# driver.net
KiCad netlist of a schematic drawn in EAGLE
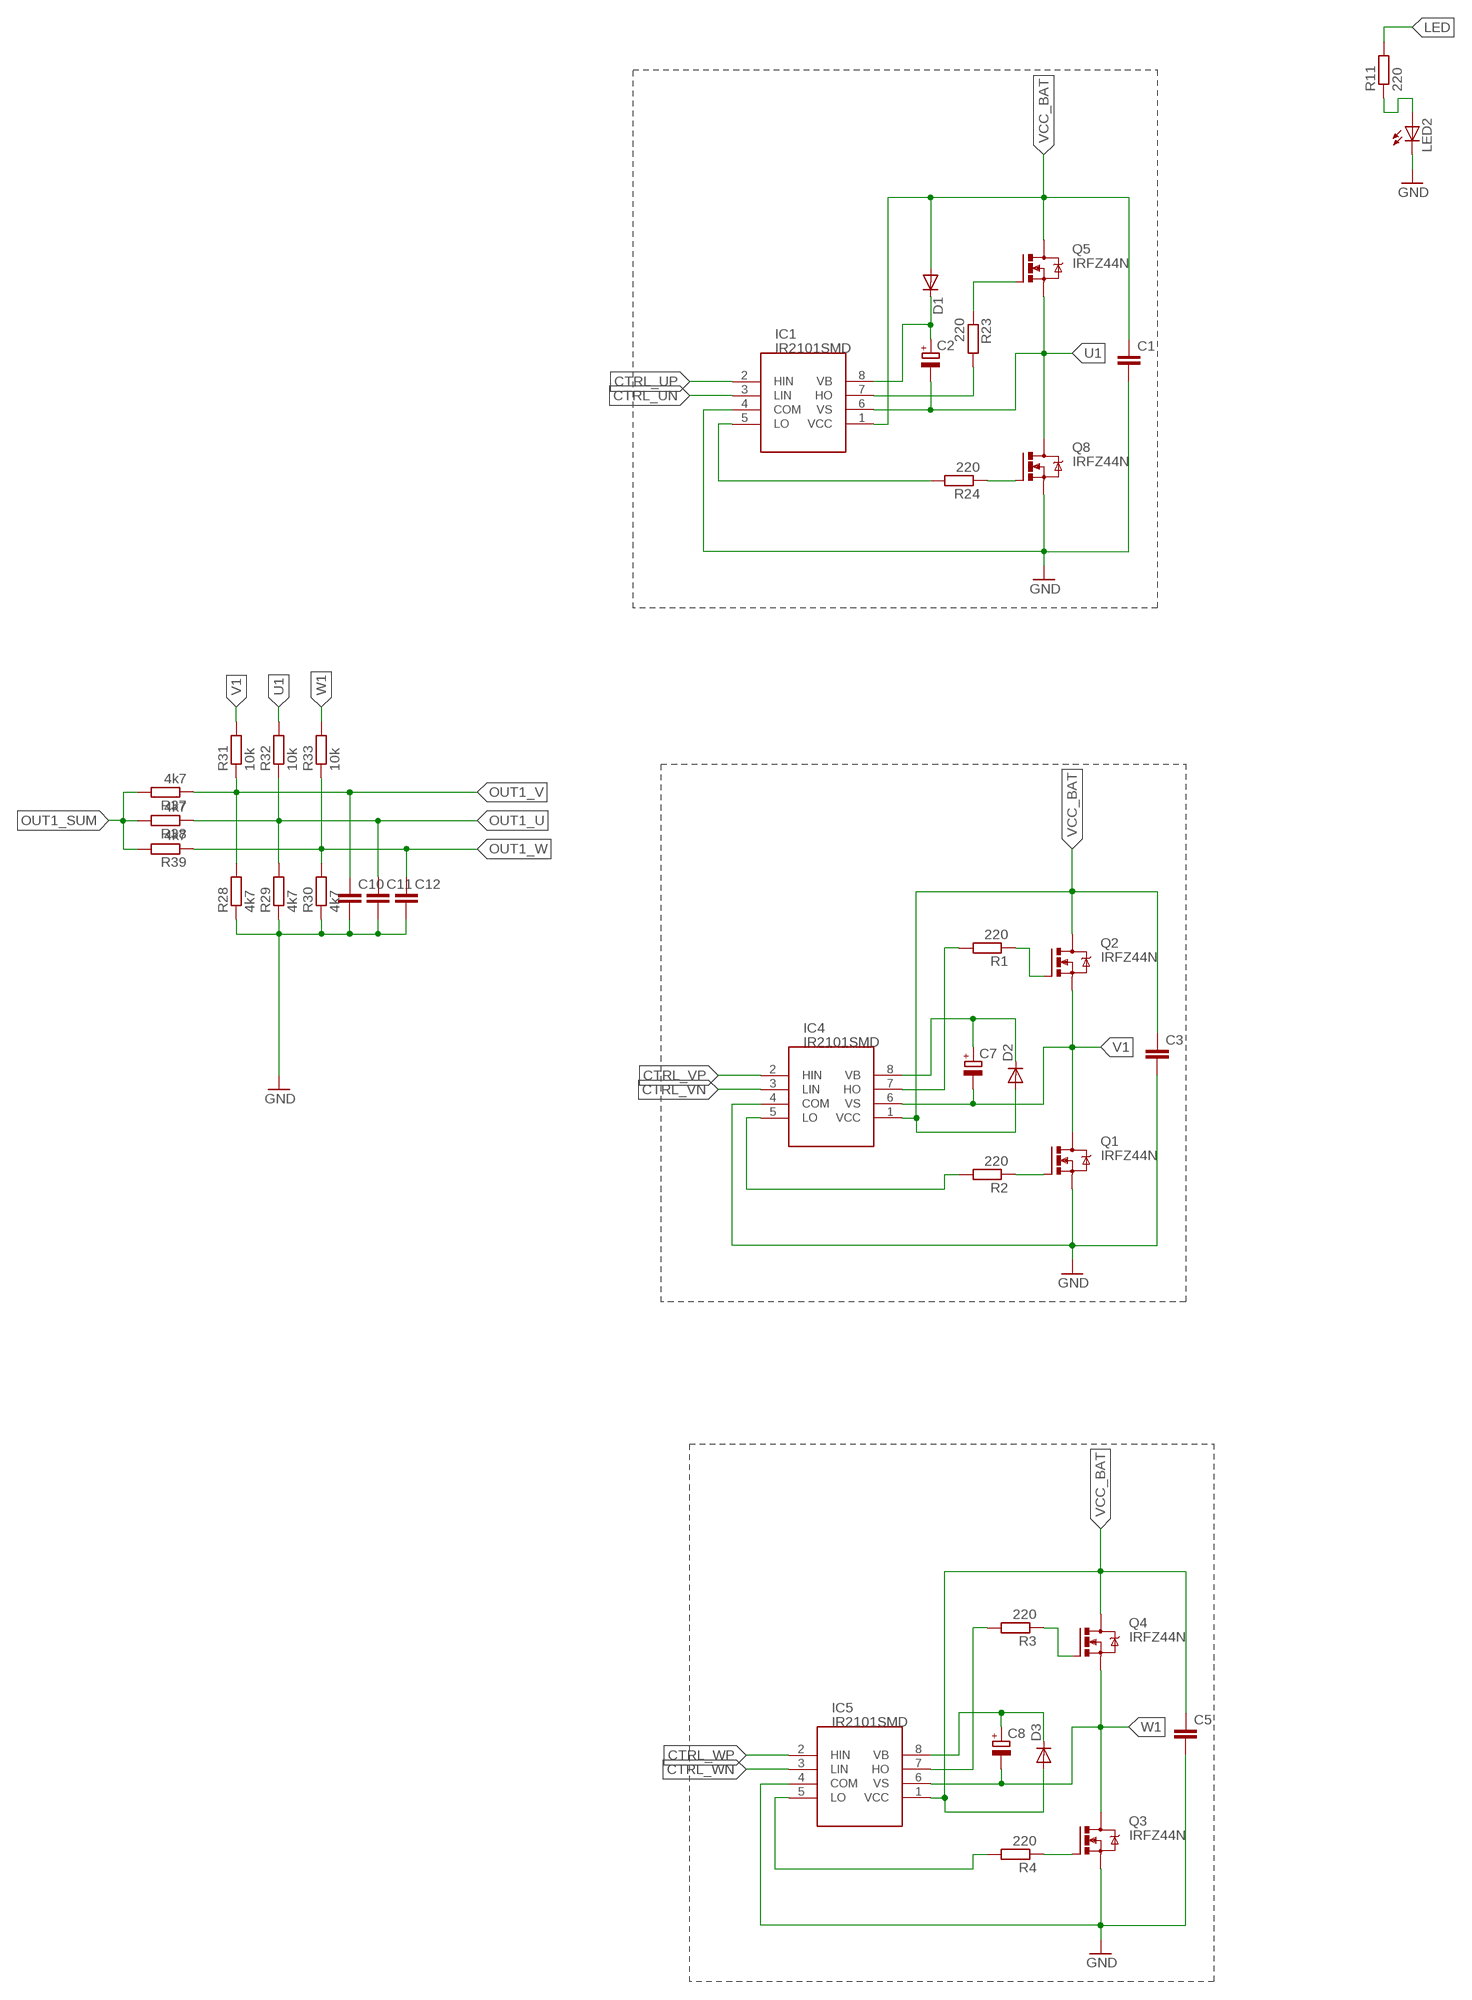
[diagram p0: schematic, sheet 1, part 1 of 2]
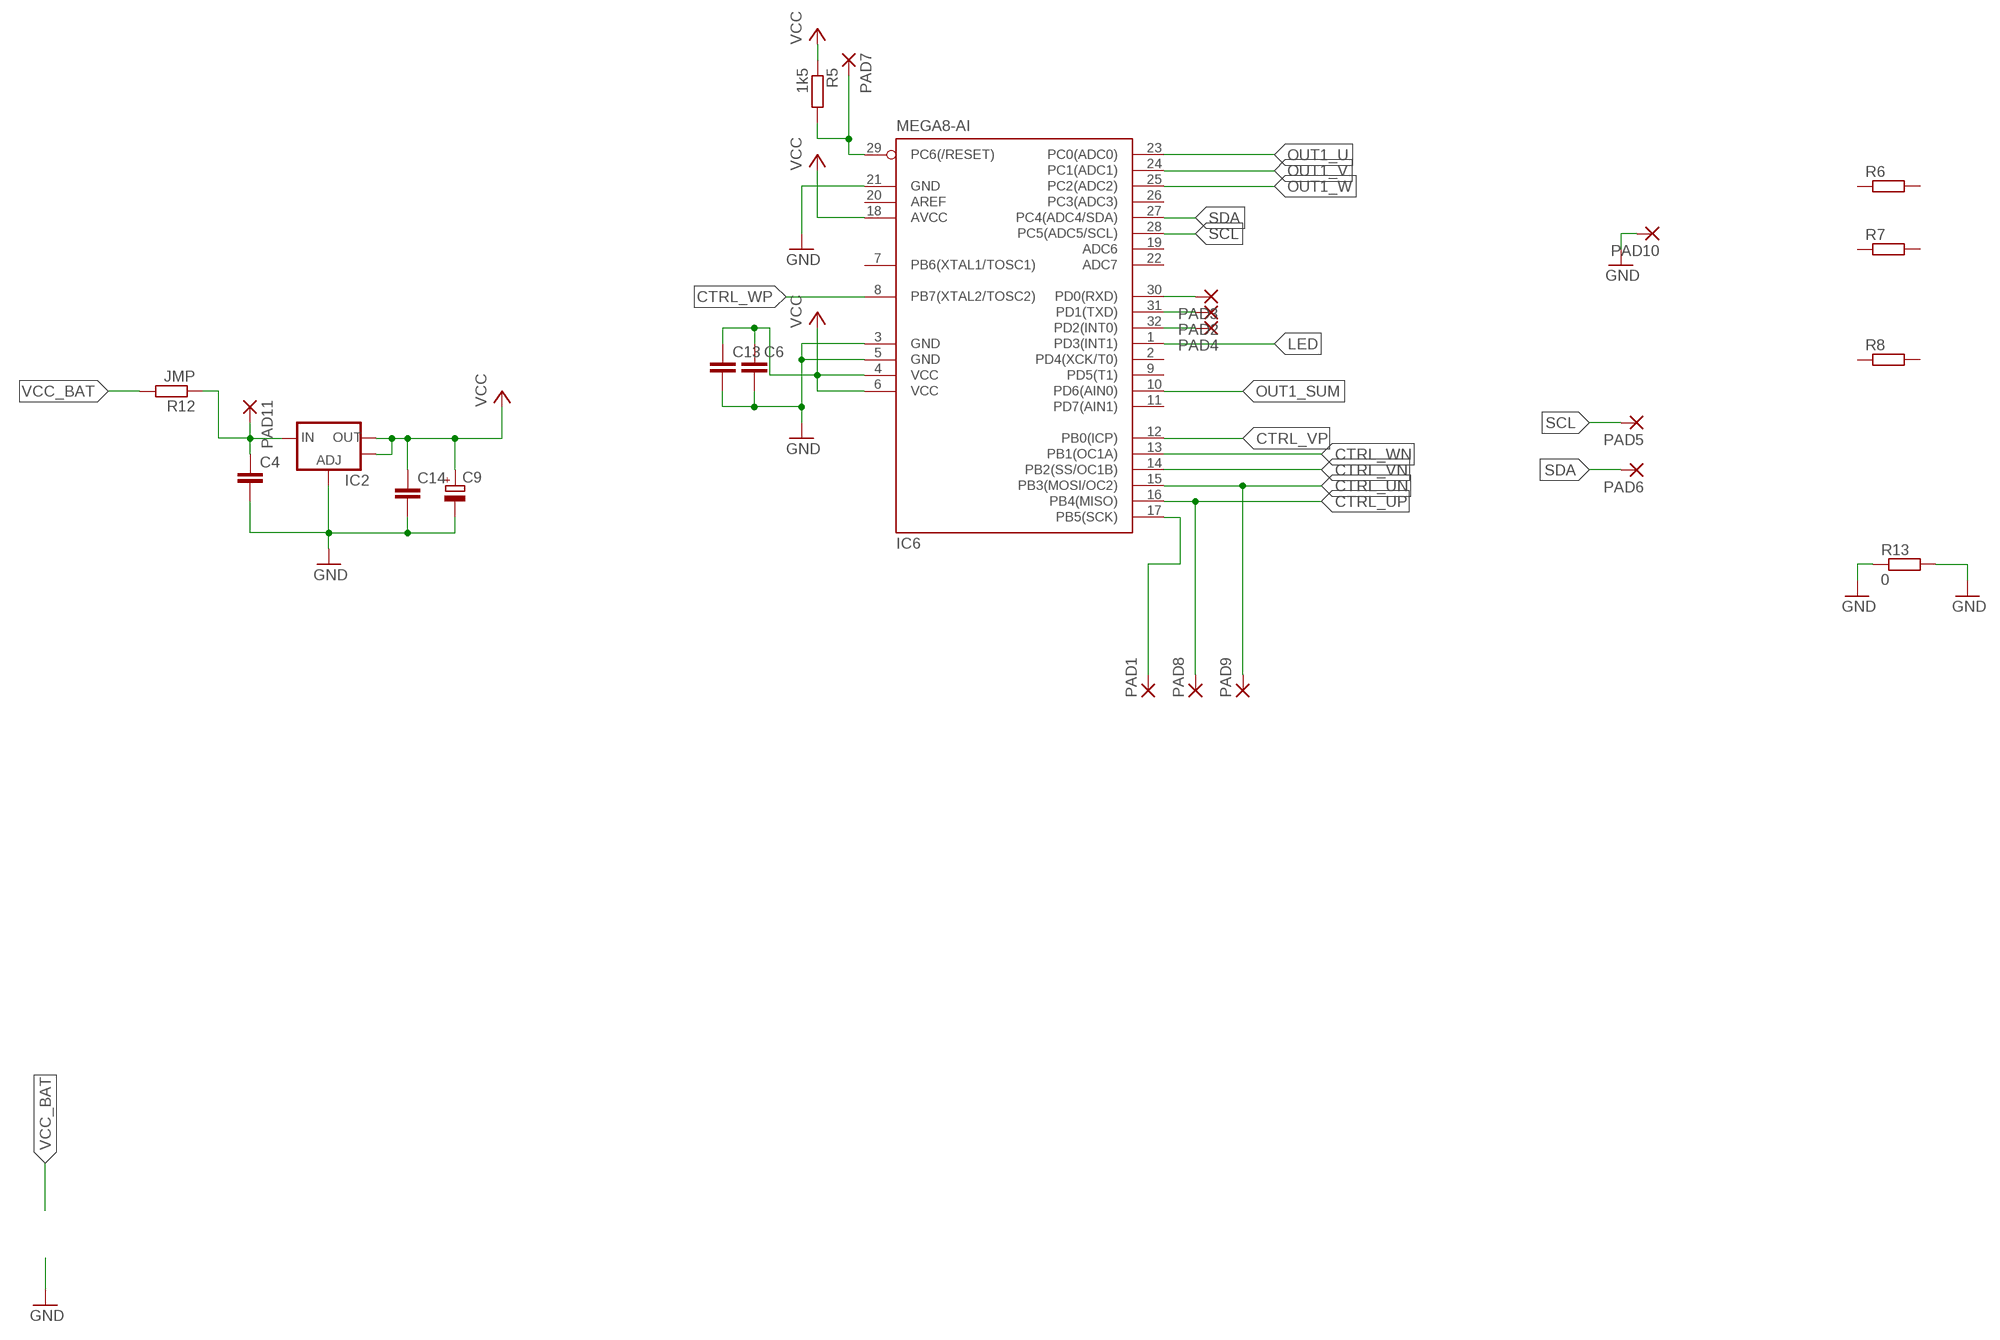
[diagram p1: schematic, sheet 1, part 2 of 2]

(export (version "E")
  (design (tool "Eeschema 10.0.6"))
  (components
    (comp (ref "C1")
      (value "C-EUC0805")
      (footprint "eagle-import:C0805")
      (libsource (lib "eagle-import") (part "C-EUC0805"))
    )
    (comp (ref "C2")
      (value "CPOL-EUSANYO_SMD_A5")
      (footprint "eagle-import:SANYO-OSCON_SMD_A5")
      (libsource (lib "eagle-import") (part "CPOL-EUSANYO_SMD_A5"))
    )
    (comp (ref "C3")
      (value "C-EUC0805")
      (footprint "eagle-import:C0805")
      (libsource (lib "eagle-import") (part "C-EUC0805"))
    )
    (comp (ref "C4")
      (value "C-EUC0805")
      (footprint "eagle-import:C0805")
      (libsource (lib "eagle-import") (part "C-EUC0805"))
    )
    (comp (ref "C5")
      (value "C-EUC0805")
      (footprint "eagle-import:C0805")
      (libsource (lib "eagle-import") (part "C-EUC0805"))
    )
    (comp (ref "C6")
      (value "C-EUC0805")
      (footprint "eagle-import:C0805")
      (libsource (lib "eagle-import") (part "C-EUC0805"))
    )
    (comp (ref "C7")
      (value "CPOL-EUSANYO_SMD_A5")
      (footprint "eagle-import:SANYO-OSCON_SMD_A5")
      (libsource (lib "eagle-import") (part "CPOL-EUSANYO_SMD_A5"))
    )
    (comp (ref "C8")
      (value "CPOL-EUSANYO_SMD_A5")
      (footprint "eagle-import:SANYO-OSCON_SMD_A5")
      (libsource (lib "eagle-import") (part "CPOL-EUSANYO_SMD_A5"))
    )
    (comp (ref "C9")
      (value "CPOL-EUSANYO_SMD_A5")
      (footprint "eagle-import:SANYO-OSCON_SMD_A5")
      (libsource (lib "eagle-import") (part "CPOL-EUSANYO_SMD_A5"))
    )
    (comp (ref "C10")
      (value "C-EUC0805")
      (footprint "eagle-import:C0805")
      (libsource (lib "eagle-import") (part "C-EUC0805"))
    )
    (comp (ref "C11")
      (value "C-EUC1206")
      (footprint "eagle-import:C1206")
      (libsource (lib "eagle-import") (part "C-EUC1206"))
    )
    (comp (ref "C12")
      (value "C-EUC1206")
      (footprint "eagle-import:C1206")
      (libsource (lib "eagle-import") (part "C-EUC1206"))
    )
    (comp (ref "C13")
      (value "C-EUC0805")
      (footprint "eagle-import:C0805")
      (libsource (lib "eagle-import") (part "C-EUC0805"))
    )
    (comp (ref "C14")
      (value "C-EUC0805")
      (footprint "eagle-import:C0805")
      (libsource (lib "eagle-import") (part "C-EUC0805"))
    )
    (comp (ref "D1")
      (value "DIODE-MINIMELF")
      (footprint "eagle-import:MINIMELF")
      (libsource (lib "eagle-import") (part "DIODE-MINIMELF"))
    )
    (comp (ref "D2")
      (value "DIODE-MINIMELF")
      (footprint "eagle-import:MINIMELF")
      (libsource (lib "eagle-import") (part "DIODE-MINIMELF"))
    )
    (comp (ref "D3")
      (value "DIODE-MINIMELF")
      (footprint "eagle-import:MINIMELF")
      (libsource (lib "eagle-import") (part "DIODE-MINIMELF"))
    )
    (comp (ref "IC1")
      (value "IR2101SMD")
      (footprint "eagle-import:SO08")
      (libsource (lib "eagle-import") (part "IR2101SMD"))
    )
    (comp (ref "IC2")
      (value "V_REG_LM1117SOT223")
      (footprint "eagle-import:SOT223")
      (libsource (lib "eagle-import") (part "V_REG_LM1117SOT223"))
    )
    (comp (ref "IC4")
      (value "IR2101SMD")
      (footprint "eagle-import:SO08")
      (libsource (lib "eagle-import") (part "IR2101SMD"))
    )
    (comp (ref "IC5")
      (value "IR2101SMD")
      (footprint "eagle-import:SO08")
      (libsource (lib "eagle-import") (part "IR2101SMD"))
    )
    (comp (ref "IC6")
      (value "MEGA8-AI")
      (footprint "eagle-import:TQFP32-08")
      (fields (field (name "MPN") "ATMEGA8-16AU"))
      (libsource (lib "eagle-import") (part "MEGA8-AI"))
    )
    (comp (ref "LED2")
      (value "LEDCHIPLED_0805")
      (footprint "eagle-import:CHIPLED_0805")
      (libsource (lib "eagle-import") (part "LEDCHIPLED_0805"))
    )
    (comp (ref "PAD1")
      (value "SMD2")
      (footprint "eagle-import:SMD1,27-2,54")
      (libsource (lib "eagle-import") (part "SMD2"))
    )
    (comp (ref "PAD2")
      (value "SMD2")
      (footprint "eagle-import:SMD1,27-2,54")
      (libsource (lib "eagle-import") (part "SMD2"))
    )
    (comp (ref "PAD3")
      (value "SMD2")
      (footprint "eagle-import:SMD1,27-2,54")
      (libsource (lib "eagle-import") (part "SMD2"))
    )
    (comp (ref "PAD4")
      (value "SMD2")
      (footprint "eagle-import:SMD1,27-2,54")
      (libsource (lib "eagle-import") (part "SMD2"))
    )
    (comp (ref "PAD5")
      (value "SMD5")
      (footprint "eagle-import:SMD2,54-5,08")
      (libsource (lib "eagle-import") (part "SMD5"))
    )
    (comp (ref "PAD6")
      (value "SMD5")
      (footprint "eagle-import:SMD2,54-5,08")
      (libsource (lib "eagle-import") (part "SMD5"))
    )
    (comp (ref "PAD7")
      (value "SMD2")
      (footprint "eagle-import:SMD1,27-2,54")
      (libsource (lib "eagle-import") (part "SMD2"))
    )
    (comp (ref "PAD8")
      (value "SMD2")
      (footprint "eagle-import:SMD1,27-2,54")
      (libsource (lib "eagle-import") (part "SMD2"))
    )
    (comp (ref "PAD9")
      (value "SMD2")
      (footprint "eagle-import:SMD1,27-2,54")
      (libsource (lib "eagle-import") (part "SMD2"))
    )
    (comp (ref "PAD10")
      (value "SMD5")
      (footprint "eagle-import:SMD2,54-5,08")
      (libsource (lib "eagle-import") (part "SMD5"))
    )
    (comp (ref "PAD11")
      (value "SMD5")
      (footprint "eagle-import:SMD2,54-5,08")
      (libsource (lib "eagle-import") (part "SMD5"))
    )
    (comp (ref "Q1")
      (value "IRFZ44N")
      (footprint "eagle-import:TO220BH-FILL")
      (libsource (lib "eagle-import") (part "IRFZ48"))
    )
    (comp (ref "Q2")
      (value "IRFZ44N")
      (footprint "eagle-import:TO220BH-FILL")
      (libsource (lib "eagle-import") (part "IRFZ48"))
    )
    (comp (ref "Q3")
      (value "IRFZ44N")
      (footprint "eagle-import:TO220BH-FILL")
      (libsource (lib "eagle-import") (part "IRFZ48"))
    )
    (comp (ref "Q4")
      (value "IRFZ44N")
      (footprint "eagle-import:TO220BH-FILL")
      (libsource (lib "eagle-import") (part "IRFZ48"))
    )
    (comp (ref "Q5")
      (value "IRFZ44N")
      (footprint "eagle-import:TO220BH-FILL")
      (libsource (lib "eagle-import") (part "IRFZ48"))
    )
    (comp (ref "Q8")
      (value "IRFZ44N")
      (footprint "eagle-import:TO220BH-FILL")
      (libsource (lib "eagle-import") (part "IRFZ48"))
    )
    (comp (ref "R1")
      (value "220")
      (footprint "eagle-import:R1206")
      (libsource (lib "eagle-import") (part "R-EU_R1206"))
    )
    (comp (ref "R2")
      (value "220")
      (footprint "eagle-import:R1206")
      (libsource (lib "eagle-import") (part "R-EU_R1206"))
    )
    (comp (ref "R3")
      (value "220")
      (footprint "eagle-import:R1206")
      (libsource (lib "eagle-import") (part "R-EU_R1206"))
    )
    (comp (ref "R4")
      (value "220")
      (footprint "eagle-import:R1206")
      (libsource (lib "eagle-import") (part "R-EU_R1206"))
    )
    (comp (ref "R5")
      (value "1k5")
      (footprint "eagle-import:R1206")
      (libsource (lib "eagle-import") (part "R-EU_R1206"))
    )
    (comp (ref "R6")
      (value "R-EU_R1206")
      (footprint "eagle-import:R1206")
      (libsource (lib "eagle-import") (part "R-EU_R1206"))
    )
    (comp (ref "R7")
      (value "R-EU_R1206")
      (footprint "eagle-import:R1206")
      (libsource (lib "eagle-import") (part "R-EU_R1206"))
    )
    (comp (ref "R8")
      (value "R-EU_R1206")
      (footprint "eagle-import:R1206")
      (libsource (lib "eagle-import") (part "R-EU_R1206"))
    )
    (comp (ref "R11")
      (value "220")
      (footprint "eagle-import:R0805")
      (libsource (lib "eagle-import") (part "resistor_R-EU_R0805"))
    )
    (comp (ref "R12")
      (value "JMP")
      (footprint "eagle-import:R0805")
      (libsource (lib "eagle-import") (part "resistor_R-EU_R0805"))
    )
    (comp (ref "R13")
      (value "0")
      (footprint "eagle-import:R1206")
      (libsource (lib "eagle-import") (part "R-EU_R1206"))
    )
    (comp (ref "R23")
      (value "220")
      (footprint "eagle-import:R1206")
      (libsource (lib "eagle-import") (part "R-EU_R1206"))
    )
    (comp (ref "R24")
      (value "220")
      (footprint "eagle-import:R1206")
      (libsource (lib "eagle-import") (part "R-EU_R1206"))
    )
    (comp (ref "R28")
      (value "4k7")
      (footprint "eagle-import:R0805")
      (libsource (lib "eagle-import") (part "R-EU_R0805"))
    )
    (comp (ref "R29")
      (value "4k7")
      (footprint "eagle-import:R1206")
      (libsource (lib "eagle-import") (part "R-EU_R1206"))
    )
    (comp (ref "R30")
      (value "4k7")
      (footprint "eagle-import:R1206")
      (libsource (lib "eagle-import") (part "R-EU_R1206"))
    )
    (comp (ref "R31")
      (value "10k")
      (footprint "eagle-import:R0805")
      (libsource (lib "eagle-import") (part "R-EU_R0805"))
    )
    (comp (ref "R32")
      (value "10k")
      (footprint "eagle-import:R1206")
      (libsource (lib "eagle-import") (part "R-EU_R1206"))
    )
    (comp (ref "R33")
      (value "10k")
      (footprint "eagle-import:R1206")
      (libsource (lib "eagle-import") (part "R-EU_R1206"))
    )
    (comp (ref "R37")
      (value "4k7")
      (footprint "eagle-import:R0805")
      (libsource (lib "eagle-import") (part "R-EU_R0805"))
    )
    (comp (ref "R38")
      (value "4k7")
      (footprint "eagle-import:R0805")
      (libsource (lib "eagle-import") (part "R-EU_R0805"))
    )
    (comp (ref "R39")
      (value "4k7")
      (footprint "eagle-import:R1206")
      (libsource (lib "eagle-import") (part "R-EU_R1206"))
    )
  )
  (nets
    (net (code "1") (name "CTRL_UN") (class "Default")
      (node (ref "IC1") (pin "3") (pinfunction "LIN_3") (pintype "bidirectional"))
      (node (ref "IC6") (pin "15") (pinfunction "PB3(MOSI/OC2)_15") (pintype "bidirectional"))
      (node (ref "PAD9") (pin "1") (pinfunction "P_1") (pintype "passive"))
    )
    (net (code "2") (name "CTRL_UP") (class "Default")
      (node (ref "IC1") (pin "2") (pinfunction "HIN_2") (pintype "bidirectional"))
      (node (ref "IC6") (pin "16") (pinfunction "PB4(MISO)_16") (pintype "bidirectional"))
      (node (ref "PAD8") (pin "1") (pinfunction "P_1") (pintype "passive"))
    )
    (net (code "3") (name "CTRL_VN") (class "Default")
      (node (ref "IC4") (pin "3") (pinfunction "LIN_3") (pintype "bidirectional"))
      (node (ref "IC6") (pin "14") (pinfunction "PB2(SS/OC1B)_14") (pintype "bidirectional"))
    )
    (net (code "4") (name "CTRL_VP") (class "Default")
      (node (ref "IC4") (pin "2") (pinfunction "HIN_2") (pintype "bidirectional"))
      (node (ref "IC6") (pin "12") (pinfunction "PB0(ICP)_12") (pintype "bidirectional"))
    )
    (net (code "5") (name "CTRL_WN") (class "Default")
      (node (ref "IC5") (pin "3") (pinfunction "LIN_3") (pintype "bidirectional"))
      (node (ref "IC6") (pin "13") (pinfunction "PB1(OC1A)_13") (pintype "bidirectional"))
    )
    (net (code "6") (name "CTRL_WP") (class "Default")
      (node (ref "IC5") (pin "2") (pinfunction "HIN_2") (pintype "bidirectional"))
      (node (ref "IC6") (pin "8") (pinfunction "PB7(XTAL2/TOSC2)_8") (pintype "bidirectional"))
    )
    (net (code "7") (name "GND") (class "Default")
      (node (ref "C1") (pin "2") (pinfunction "2_2") (pintype "passive"))
      (node (ref "C10") (pin "2") (pinfunction "2_2") (pintype "passive"))
      (node (ref "C11") (pin "2") (pinfunction "2_2") (pintype "passive"))
      (node (ref "C12") (pin "2") (pinfunction "2_2") (pintype "passive"))
      (node (ref "C13") (pin "2") (pinfunction "2_2") (pintype "passive"))
      (node (ref "C14") (pin "2") (pinfunction "2_2") (pintype "passive"))
      (node (ref "C3") (pin "2") (pinfunction "2_2") (pintype "passive"))
      (node (ref "C4") (pin "2") (pinfunction "2_2") (pintype "passive"))
      (node (ref "C5") (pin "2") (pinfunction "2_2") (pintype "passive"))
      (node (ref "C6") (pin "2") (pinfunction "2_2") (pintype "passive"))
      (node (ref "C9") (pin "-") (pinfunction "-_-") (pintype "passive"))
      (node (ref "IC1") (pin "4") (pinfunction "COM_4") (pintype "bidirectional"))
      (node (ref "IC2") (pin "1") (pinfunction "ADJ_1") (pintype "input"))
      (node (ref "IC4") (pin "4") (pinfunction "COM_4") (pintype "bidirectional"))
      (node (ref "IC5") (pin "4") (pinfunction "COM_4") (pintype "bidirectional"))
      (node (ref "IC6") (pin "21") (pinfunction "GND_21") (pintype "power_in"))
      (node (ref "IC6") (pin "3") (pinfunction "GND_3") (pintype "power_in"))
      (node (ref "IC6") (pin "5") (pinfunction "GND_5") (pintype "power_in"))
      (node (ref "LED2") (pin "C") (pinfunction "C_C") (pintype "passive"))
      (node (ref "PAD10") (pin "1") (pinfunction "P_1") (pintype "passive"))
      (node (ref "Q1") (pin "S") (pinfunction "S_S") (pintype "passive"))
      (node (ref "Q3") (pin "S") (pinfunction "S_S") (pintype "passive"))
      (node (ref "Q8") (pin "S") (pinfunction "S_S") (pintype "passive"))
      (node (ref "R13") (pin "1") (pinfunction "1_1") (pintype "passive"))
      (node (ref "R13") (pin "2") (pinfunction "2_2") (pintype "passive"))
      (node (ref "R28") (pin "1") (pinfunction "1_1") (pintype "passive"))
      (node (ref "R29") (pin "1") (pinfunction "1_1") (pintype "passive"))
      (node (ref "R30") (pin "1") (pinfunction "1_1") (pintype "passive"))
    )
    (net (code "8") (name "LED") (class "Default")
      (node (ref "IC6") (pin "1") (pinfunction "PD3(INT1)_1") (pintype "bidirectional"))
      (node (ref "R11") (pin "2") (pinfunction "2_2") (pintype "passive"))
    )
    (net (code "9") (name "Net-(IC1-HO)") (class "Default")
      (node (ref "IC1") (pin "7") (pinfunction "HO_7") (pintype "bidirectional"))
      (node (ref "R23") (pin "2") (pinfunction "2_2") (pintype "passive"))
    )
    (net (code "10") (name "Net-(IC1-LO)") (class "Default")
      (node (ref "IC1") (pin "5") (pinfunction "LO_5") (pintype "bidirectional"))
      (node (ref "R24") (pin "2") (pinfunction "2_2") (pintype "passive"))
    )
    (net (code "11") (name "Net-(IC1-VB)") (class "Default")
      (node (ref "C2") (pin "+") (pinfunction "+_+") (pintype "passive"))
      (node (ref "D1") (pin "C") (pinfunction "C_C") (pintype "passive"))
      (node (ref "IC1") (pin "8") (pinfunction "VB_8") (pintype "bidirectional"))
    )
    (net (code "12") (name "Net-(IC2-IN)") (class "Default")
      (node (ref "C4") (pin "1") (pinfunction "1_1") (pintype "passive"))
      (node (ref "IC2") (pin "3") (pinfunction "IN_3") (pintype "input"))
      (node (ref "PAD11") (pin "1") (pinfunction "P_1") (pintype "passive"))
      (node (ref "R12") (pin "1") (pinfunction "1_1") (pintype "passive"))
    )
    (net (code "13") (name "Net-(IC4-HO)") (class "Default")
      (node (ref "IC4") (pin "7") (pinfunction "HO_7") (pintype "bidirectional"))
      (node (ref "R1") (pin "2") (pinfunction "2_2") (pintype "passive"))
    )
    (net (code "14") (name "Net-(IC4-LO)") (class "Default")
      (node (ref "IC4") (pin "5") (pinfunction "LO_5") (pintype "bidirectional"))
      (node (ref "R2") (pin "2") (pinfunction "2_2") (pintype "passive"))
    )
    (net (code "15") (name "Net-(IC4-VB)") (class "Default")
      (node (ref "C7") (pin "+") (pinfunction "+_+") (pintype "passive"))
      (node (ref "D2") (pin "C") (pinfunction "C_C") (pintype "passive"))
      (node (ref "IC4") (pin "8") (pinfunction "VB_8") (pintype "bidirectional"))
    )
    (net (code "16") (name "Net-(IC5-HO)") (class "Default")
      (node (ref "IC5") (pin "7") (pinfunction "HO_7") (pintype "bidirectional"))
      (node (ref "R3") (pin "2") (pinfunction "2_2") (pintype "passive"))
    )
    (net (code "17") (name "Net-(IC5-LO)") (class "Default")
      (node (ref "IC5") (pin "5") (pinfunction "LO_5") (pintype "bidirectional"))
      (node (ref "R4") (pin "2") (pinfunction "2_2") (pintype "passive"))
    )
    (net (code "18") (name "Net-(IC5-VB)") (class "Default")
      (node (ref "C8") (pin "+") (pinfunction "+_+") (pintype "passive"))
      (node (ref "D3") (pin "C") (pinfunction "C_C") (pintype "passive"))
      (node (ref "IC5") (pin "8") (pinfunction "VB_8") (pintype "bidirectional"))
    )
    (net (code "19") (name "Net-(IC6-PB5(SCK))") (class "Default")
      (node (ref "IC6") (pin "17") (pinfunction "PB5(SCK)_17") (pintype "bidirectional"))
      (node (ref "PAD1") (pin "1") (pinfunction "P_1") (pintype "passive"))
    )
    (net (code "20") (name "Net-(IC6-PC6({slash}RESET))") (class "Default")
      (node (ref "IC6") (pin "29") (pinfunction "PC6(/RESET)_29") (pintype "bidirectional"))
      (node (ref "PAD7") (pin "1") (pinfunction "P_1") (pintype "passive"))
      (node (ref "R5") (pin "2") (pinfunction "2_2") (pintype "passive"))
    )
    (net (code "21") (name "Net-(IC6-PD0(RXD))") (class "Default")
      (node (ref "IC6") (pin "30") (pinfunction "PD0(RXD)_30") (pintype "bidirectional"))
      (node (ref "PAD3") (pin "1") (pinfunction "P_1") (pintype "passive"))
    )
    (net (code "22") (name "Net-(IC6-PD1(TXD))") (class "Default")
      (node (ref "IC6") (pin "31") (pinfunction "PD1(TXD)_31") (pintype "bidirectional"))
      (node (ref "PAD2") (pin "1") (pinfunction "P_1") (pintype "passive"))
    )
    (net (code "23") (name "Net-(IC6-PD2(INT0))") (class "Default")
      (node (ref "IC6") (pin "32") (pinfunction "PD2(INT0)_32") (pintype "bidirectional"))
      (node (ref "PAD4") (pin "1") (pinfunction "P_1") (pintype "passive"))
    )
    (net (code "24") (name "Net-(LED2-PadA)") (class "Default")
      (node (ref "LED2") (pin "A") (pinfunction "A_A") (pintype "passive"))
      (node (ref "R11") (pin "1") (pinfunction "1_1") (pintype "passive"))
    )
    (net (code "25") (name "Net-(Q1-PadG)") (class "Default")
      (node (ref "Q1") (pin "G") (pinfunction "G_G") (pintype "passive"))
      (node (ref "R2") (pin "1") (pinfunction "1_1") (pintype "passive"))
    )
    (net (code "26") (name "Net-(Q2-PadG)") (class "Default")
      (node (ref "Q2") (pin "G") (pinfunction "G_G") (pintype "passive"))
      (node (ref "R1") (pin "1") (pinfunction "1_1") (pintype "passive"))
    )
    (net (code "27") (name "Net-(Q3-PadG)") (class "Default")
      (node (ref "Q3") (pin "G") (pinfunction "G_G") (pintype "passive"))
      (node (ref "R4") (pin "1") (pinfunction "1_1") (pintype "passive"))
    )
    (net (code "28") (name "Net-(Q4-PadG)") (class "Default")
      (node (ref "Q4") (pin "G") (pinfunction "G_G") (pintype "passive"))
      (node (ref "R3") (pin "1") (pinfunction "1_1") (pintype "passive"))
    )
    (net (code "29") (name "Net-(Q5-PadG)") (class "Default")
      (node (ref "Q5") (pin "G") (pinfunction "G_G") (pintype "passive"))
      (node (ref "R23") (pin "1") (pinfunction "1_1") (pintype "passive"))
    )
    (net (code "30") (name "Net-(Q8-PadG)") (class "Default")
      (node (ref "Q8") (pin "G") (pinfunction "G_G") (pintype "passive"))
      (node (ref "R24") (pin "1") (pinfunction "1_1") (pintype "passive"))
    )
    (net (code "31") (name "OUT1_SUM") (class "Default")
      (node (ref "IC6") (pin "10") (pinfunction "PD6(AIN0)_10") (pintype "bidirectional"))
      (node (ref "R37") (pin "2") (pinfunction "2_2") (pintype "passive"))
      (node (ref "R38") (pin "2") (pinfunction "2_2") (pintype "passive"))
      (node (ref "R39") (pin "2") (pinfunction "2_2") (pintype "passive"))
    )
    (net (code "32") (name "OUT1_U") (class "Default")
      (node (ref "C11") (pin "1") (pinfunction "1_1") (pintype "passive"))
      (node (ref "IC6") (pin "23") (pinfunction "PC0(ADC0)_23") (pintype "bidirectional"))
      (node (ref "R29") (pin "2") (pinfunction "2_2") (pintype "passive"))
      (node (ref "R32") (pin "1") (pinfunction "1_1") (pintype "passive"))
      (node (ref "R38") (pin "1") (pinfunction "1_1") (pintype "passive"))
    )
    (net (code "33") (name "OUT1_V") (class "Default")
      (node (ref "C10") (pin "1") (pinfunction "1_1") (pintype "passive"))
      (node (ref "IC6") (pin "24") (pinfunction "PC1(ADC1)_24") (pintype "bidirectional"))
      (node (ref "R28") (pin "2") (pinfunction "2_2") (pintype "passive"))
      (node (ref "R31") (pin "1") (pinfunction "1_1") (pintype "passive"))
      (node (ref "R37") (pin "1") (pinfunction "1_1") (pintype "passive"))
    )
    (net (code "34") (name "OUT1_W") (class "Default")
      (node (ref "C12") (pin "1") (pinfunction "1_1") (pintype "passive"))
      (node (ref "IC6") (pin "25") (pinfunction "PC2(ADC2)_25") (pintype "bidirectional"))
      (node (ref "R30") (pin "2") (pinfunction "2_2") (pintype "passive"))
      (node (ref "R33") (pin "1") (pinfunction "1_1") (pintype "passive"))
      (node (ref "R39") (pin "1") (pinfunction "1_1") (pintype "passive"))
    )
    (net (code "35") (name "SCL") (class "Default")
      (node (ref "IC6") (pin "28") (pinfunction "PC5(ADC5/SCL)_28") (pintype "bidirectional"))
      (node (ref "PAD5") (pin "1") (pinfunction "P_1") (pintype "passive"))
    )
    (net (code "36") (name "SDA") (class "Default")
      (node (ref "IC6") (pin "27") (pinfunction "PC4(ADC4/SDA)_27") (pintype "bidirectional"))
      (node (ref "PAD6") (pin "1") (pinfunction "P_1") (pintype "passive"))
    )
    (net (code "37") (name "U1") (class "Default")
      (node (ref "C2") (pin "-") (pinfunction "-_-") (pintype "passive"))
      (node (ref "IC1") (pin "6") (pinfunction "VS_6") (pintype "bidirectional"))
      (node (ref "Q5") (pin "S") (pinfunction "S_S") (pintype "passive"))
      (node (ref "Q8") (pin "D") (pinfunction "D_D") (pintype "passive"))
      (node (ref "R32") (pin "2") (pinfunction "2_2") (pintype "passive"))
    )
    (net (code "38") (name "V1") (class "Default")
      (node (ref "C7") (pin "-") (pinfunction "-_-") (pintype "passive"))
      (node (ref "IC4") (pin "6") (pinfunction "VS_6") (pintype "bidirectional"))
      (node (ref "Q1") (pin "D") (pinfunction "D_D") (pintype "passive"))
      (node (ref "Q2") (pin "S") (pinfunction "S_S") (pintype "passive"))
      (node (ref "R31") (pin "2") (pinfunction "2_2") (pintype "passive"))
    )
    (net (code "39") (name "VCC") (class "Default")
      (node (ref "C13") (pin "1") (pinfunction "1_1") (pintype "passive"))
      (node (ref "C14") (pin "1") (pinfunction "1_1") (pintype "passive"))
      (node (ref "C6") (pin "1") (pinfunction "1_1") (pintype "passive"))
      (node (ref "C9") (pin "+") (pinfunction "+_+") (pintype "passive"))
      (node (ref "IC2") (pin "2") (pinfunction "OUT_2") (pintype "output"))
      (node (ref "IC2") (pin "4") (pinfunction "OUT_4") (pintype "output"))
      (node (ref "IC6") (pin "18") (pinfunction "AVCC_18") (pintype "power_in"))
      (node (ref "IC6") (pin "4") (pinfunction "VCC_4") (pintype "power_in"))
      (node (ref "IC6") (pin "6") (pinfunction "VCC_6") (pintype "power_in"))
      (node (ref "R5") (pin "1") (pinfunction "1_1") (pintype "passive"))
    )
    (net (code "40") (name "VCC_BAT") (class "Default")
      (node (ref "C1") (pin "1") (pinfunction "1_1") (pintype "passive"))
      (node (ref "C3") (pin "1") (pinfunction "1_1") (pintype "passive"))
      (node (ref "C5") (pin "1") (pinfunction "1_1") (pintype "passive"))
      (node (ref "D1") (pin "A") (pinfunction "A_A") (pintype "passive"))
      (node (ref "D2") (pin "A") (pinfunction "A_A") (pintype "passive"))
      (node (ref "D3") (pin "A") (pinfunction "A_A") (pintype "passive"))
      (node (ref "IC1") (pin "1") (pinfunction "VCC_1") (pintype "bidirectional"))
      (node (ref "IC4") (pin "1") (pinfunction "VCC_1") (pintype "bidirectional"))
      (node (ref "IC5") (pin "1") (pinfunction "VCC_1") (pintype "bidirectional"))
      (node (ref "Q2") (pin "D") (pinfunction "D_D") (pintype "passive"))
      (node (ref "Q4") (pin "D") (pinfunction "D_D") (pintype "passive"))
      (node (ref "Q5") (pin "D") (pinfunction "D_D") (pintype "passive"))
      (node (ref "R12") (pin "2") (pinfunction "2_2") (pintype "passive"))
    )
    (net (code "41") (name "W1") (class "Default")
      (node (ref "C8") (pin "-") (pinfunction "-_-") (pintype "passive"))
      (node (ref "IC5") (pin "6") (pinfunction "VS_6") (pintype "bidirectional"))
      (node (ref "Q3") (pin "D") (pinfunction "D_D") (pintype "passive"))
      (node (ref "Q4") (pin "S") (pinfunction "S_S") (pintype "passive"))
      (node (ref "R33") (pin "2") (pinfunction "2_2") (pintype "passive"))
    )
    (net (code "42") (name "unconnected-(IC6-ADC6-Pad19)") (class "Default")
      (node (ref "IC6") (pin "19") (pinfunction "ADC6_19") (pintype "bidirectional"))
    )
    (net (code "43") (name "unconnected-(IC6-ADC7-Pad22)") (class "Default")
      (node (ref "IC6") (pin "22") (pinfunction "ADC7_22") (pintype "bidirectional"))
    )
    (net (code "44") (name "unconnected-(IC6-AREF-Pad20)") (class "Default")
      (node (ref "IC6") (pin "20") (pinfunction "AREF_20") (pintype "passive"))
    )
    (net (code "45") (name "unconnected-(IC6-PB6(XTAL1{slash}TOSC1)-Pad7)") (class "Default")
      (node (ref "IC6") (pin "7") (pinfunction "PB6(XTAL1/TOSC1)_7") (pintype "bidirectional"))
    )
    (net (code "46") (name "unconnected-(IC6-PC3(ADC3)-Pad26)") (class "Default")
      (node (ref "IC6") (pin "26") (pinfunction "PC3(ADC3)_26") (pintype "bidirectional"))
    )
    (net (code "47") (name "unconnected-(IC6-PD4(XCK{slash}T0)-Pad2)") (class "Default")
      (node (ref "IC6") (pin "2") (pinfunction "PD4(XCK/T0)_2") (pintype "bidirectional"))
    )
    (net (code "48") (name "unconnected-(IC6-PD5(T1)-Pad9)") (class "Default")
      (node (ref "IC6") (pin "9") (pinfunction "PD5(T1)_9") (pintype "bidirectional"))
    )
    (net (code "49") (name "unconnected-(IC6-PD7(AIN1)-Pad11)") (class "Default")
      (node (ref "IC6") (pin "11") (pinfunction "PD7(AIN1)_11") (pintype "bidirectional"))
    )
    (net (code "50") (name "unconnected-(R6-Pad1)") (class "Default")
      (node (ref "R6") (pin "1") (pinfunction "1_1") (pintype "passive"))
    )
    (net (code "51") (name "unconnected-(R6-Pad2)") (class "Default")
      (node (ref "R6") (pin "2") (pinfunction "2_2") (pintype "passive"))
    )
    (net (code "52") (name "unconnected-(R7-Pad1)") (class "Default")
      (node (ref "R7") (pin "1") (pinfunction "1_1") (pintype "passive"))
    )
    (net (code "53") (name "unconnected-(R7-Pad2)") (class "Default")
      (node (ref "R7") (pin "2") (pinfunction "2_2") (pintype "passive"))
    )
    (net (code "54") (name "unconnected-(R8-Pad1)") (class "Default")
      (node (ref "R8") (pin "1") (pinfunction "1_1") (pintype "passive"))
    )
    (net (code "55") (name "unconnected-(R8-Pad2)") (class "Default")
      (node (ref "R8") (pin "2") (pinfunction "2_2") (pintype "passive"))
    )
  )
)
